# ROS-Robot-Controller.net
KiCad netlist of a schematic drawn in Altium Designer
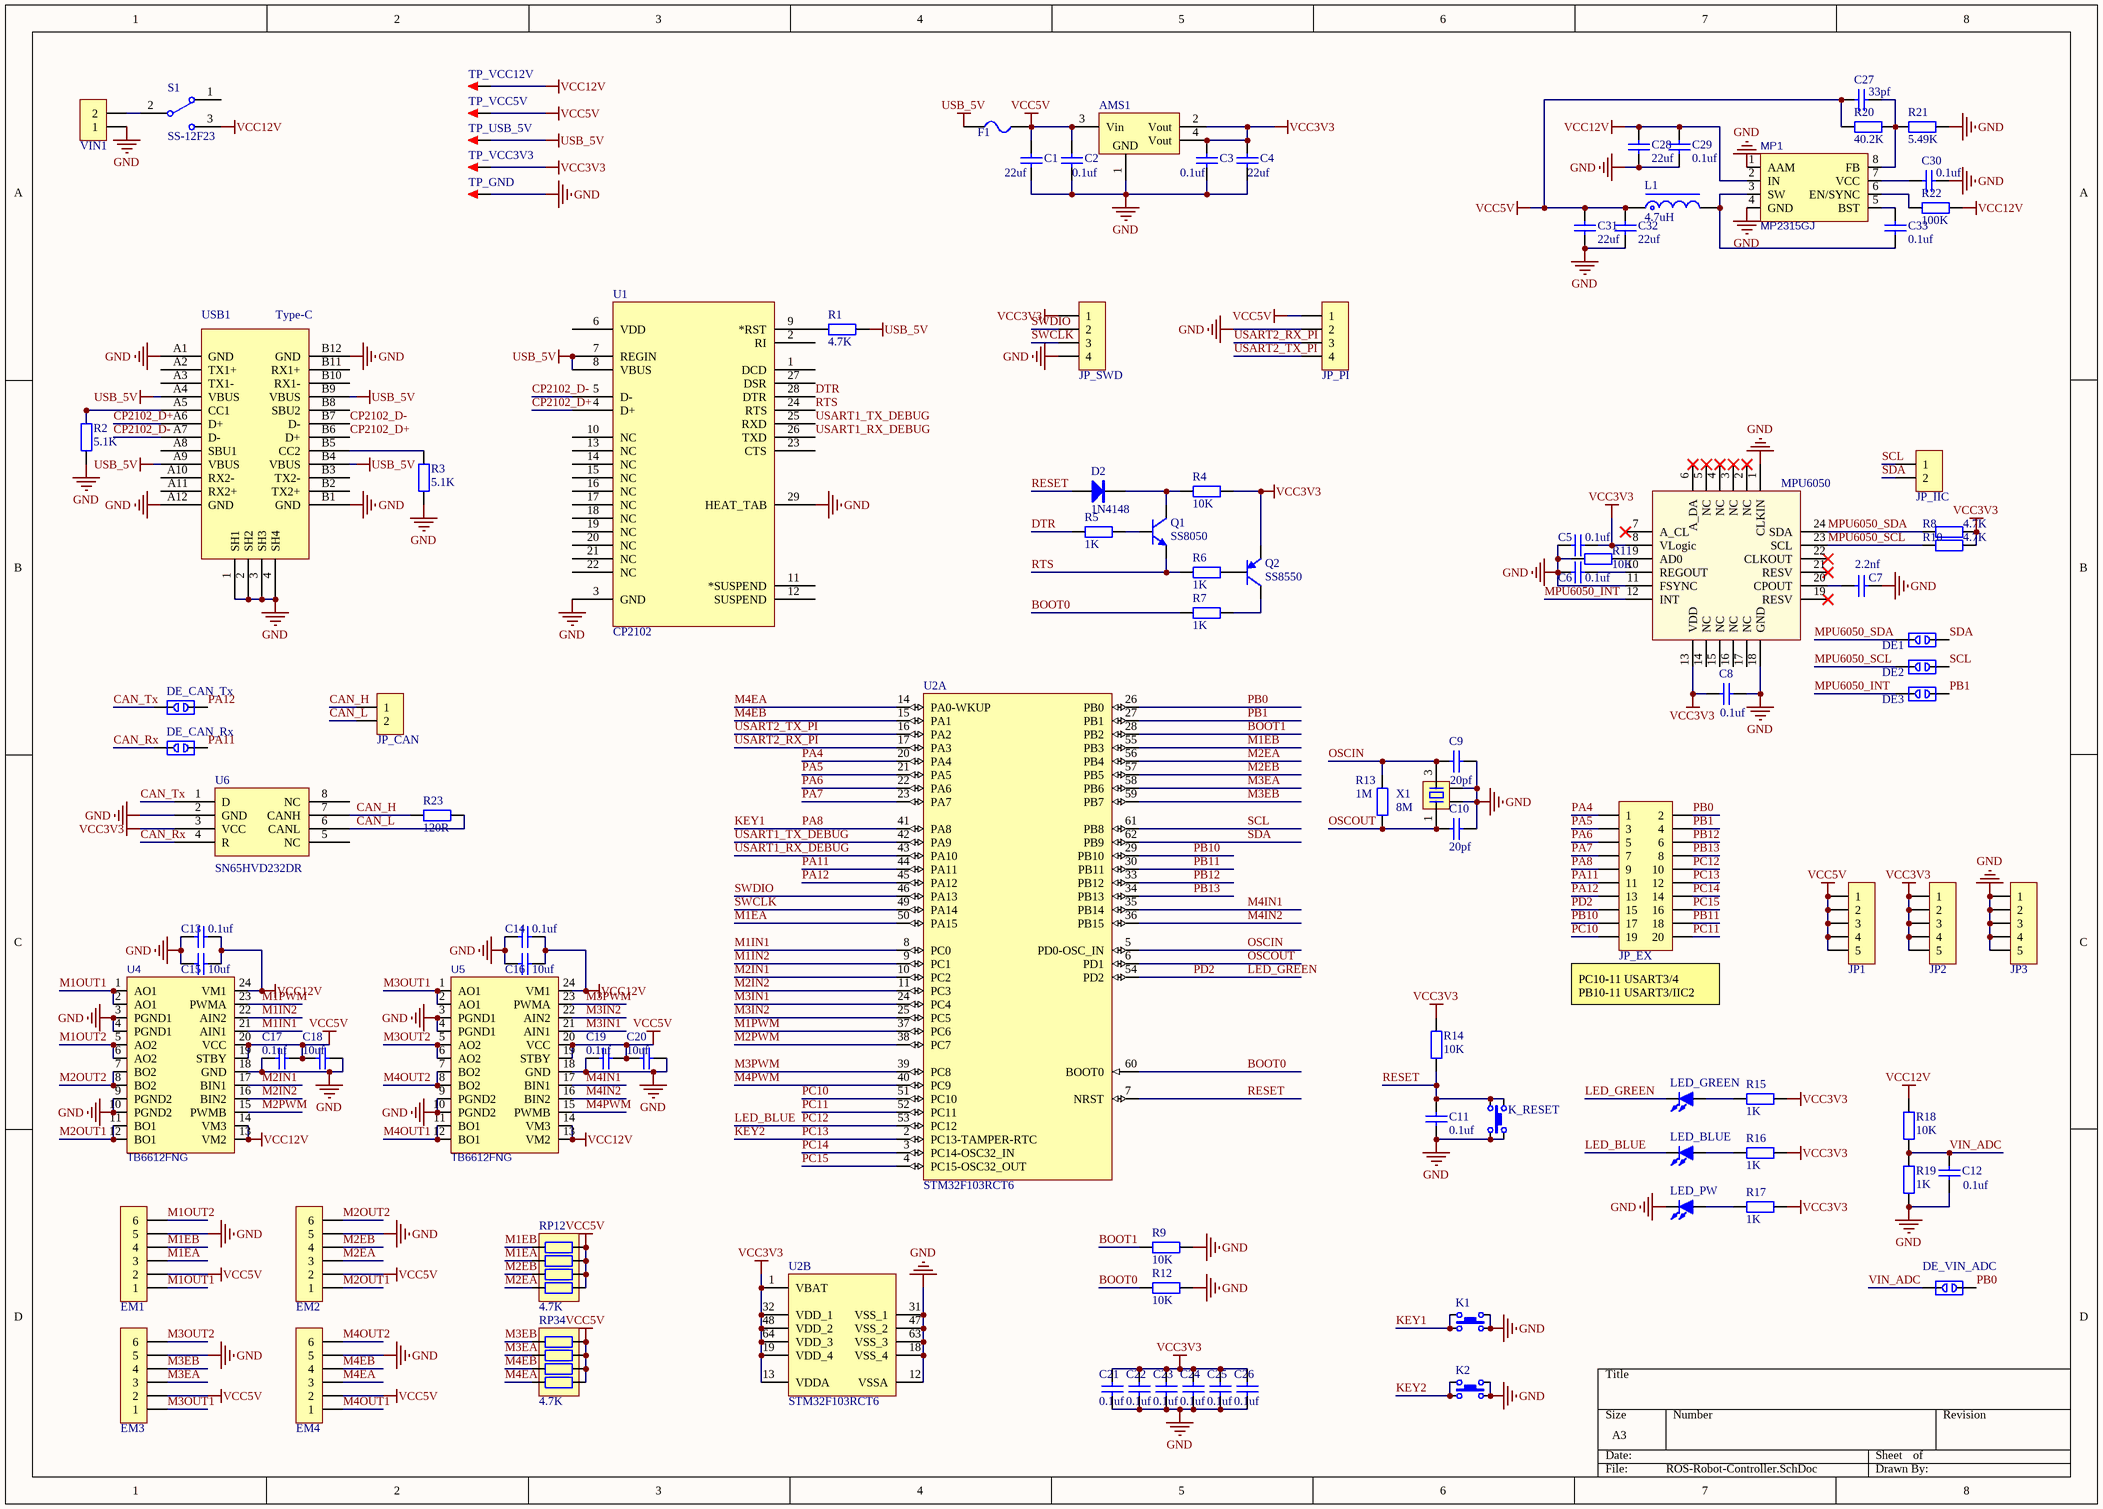
[diagram p0: ROS-Robot-Controller.SchDoc]

(export (version "E")
  (design (tool "Eeschema 10.0.6"))
  (components
    (comp (ref "AMS1")
      (value "AMS1117-3V3")
      (footprint "SOT223_L")
      (description "三端稳压芯片")
      (libsource (lib "1.1 - 电源类芯片") (part "AMS1117"))
    )
    (comp (ref "C1")
      (value "22uf")
      (footprint "C0603_L")
      (description "贴片电容")
      (libsource (lib "0.1 - 电阻-电容-电感-电位器") (part "C"))
    )
    (comp (ref "C2")
      (value "0.1uf")
      (footprint "C0603_L")
      (description "贴片电容")
      (libsource (lib "0.1 - 电阻-电容-电感-电位器") (part "C"))
    )
    (comp (ref "C3")
      (value "0.1uf")
      (footprint "C0603_L")
      (description "贴片电容")
      (libsource (lib "0.1 - 电阻-电容-电感-电位器") (part "C"))
    )
    (comp (ref "C4")
      (value "22uf")
      (footprint "C0603_L")
      (description "贴片电容")
      (libsource (lib "0.1 - 电阻-电容-电感-电位器") (part "C"))
    )
    (comp (ref "C5")
      (value "0.1uf")
      (footprint "C0402_L")
      (description "贴片电容")
      (libsource (lib "0.1 - 电阻-电容-电感-电位器") (part "C"))
    )
    (comp (ref "C6")
      (value "0.1uf")
      (footprint "C0402_L")
      (description "贴片电容")
      (libsource (lib "0.1 - 电阻-电容-电感-电位器") (part "C"))
    )
    (comp (ref "C7")
      (value "2.2nf")
      (footprint "C0402_L")
      (description "贴片电容")
      (libsource (lib "0.1 - 电阻-电容-电感-电位器") (part "C"))
    )
    (comp (ref "C8")
      (value "0.1uf")
      (footprint "C0402_L")
      (description "贴片电容")
      (libsource (lib "0.1 - 电阻-电容-电感-电位器") (part "C"))
    )
    (comp (ref "C9")
      (value "20pf")
      (footprint "C0402_L")
      (description "贴片电容")
      (libsource (lib "0.1 - 电阻-电容-电感-电位器") (part "C"))
    )
    (comp (ref "C10")
      (value "20pf")
      (footprint "C0402_L")
      (description "贴片电容")
      (libsource (lib "0.1 - 电阻-电容-电感-电位器") (part "C"))
    )
    (comp (ref "C11")
      (value "0.1uf")
      (footprint "C0402_L")
      (description "贴片电容")
      (libsource (lib "0.1 - 电阻-电容-电感-电位器") (part "C"))
    )
    (comp (ref "C12")
      (value "0.1uf")
      (footprint "C0603_L")
      (description "贴片电容")
      (libsource (lib "0.1 - 电阻-电容-电感-电位器") (part "C"))
    )
    (comp (ref "C13")
      (value "0.1uf")
      (footprint "C0603_L")
      (description "贴片电容")
      (libsource (lib "0.1 - 电阻-电容-电感-电位器") (part "C"))
    )
    (comp (ref "C14")
      (value "0.1uf")
      (footprint "C0603_L")
      (description "贴片电容")
      (libsource (lib "0.1 - 电阻-电容-电感-电位器") (part "C"))
    )
    (comp (ref "C15")
      (value "10uf")
      (footprint "C0603_L")
      (description "贴片电容")
      (libsource (lib "0.1 - 电阻-电容-电感-电位器") (part "C"))
    )
    (comp (ref "C16")
      (value "10uf")
      (footprint "C0603_L")
      (description "贴片电容")
      (libsource (lib "0.1 - 电阻-电容-电感-电位器") (part "C"))
    )
    (comp (ref "C17")
      (value "0.1uf")
      (footprint "C0402_L")
      (description "贴片电容")
      (libsource (lib "0.1 - 电阻-电容-电感-电位器") (part "C"))
    )
    (comp (ref "C18")
      (value "10uf")
      (footprint "C0402_L")
      (description "贴片电容")
      (libsource (lib "0.1 - 电阻-电容-电感-电位器") (part "C"))
    )
    (comp (ref "C19")
      (value "0.1uf")
      (footprint "C0402_L")
      (description "贴片电容")
      (libsource (lib "0.1 - 电阻-电容-电感-电位器") (part "C"))
    )
    (comp (ref "C20")
      (value "10uf")
      (footprint "C0402_L")
      (description "贴片电容")
      (libsource (lib "0.1 - 电阻-电容-电感-电位器") (part "C"))
    )
    (comp (ref "C21")
      (value "0.1uf")
      (footprint "C0402_L")
      (description "贴片电容")
      (libsource (lib "0.1 - 电阻-电容-电感-电位器") (part "C"))
    )
    (comp (ref "C22")
      (value "0.1uf")
      (footprint "C0402_L")
      (description "贴片电容")
      (libsource (lib "0.1 - 电阻-电容-电感-电位器") (part "C"))
    )
    (comp (ref "C23")
      (value "0.1uf")
      (footprint "C0402_L")
      (description "贴片电容")
      (libsource (lib "0.1 - 电阻-电容-电感-电位器") (part "C"))
    )
    (comp (ref "C24")
      (value "0.1uf")
      (footprint "C0402_L")
      (description "贴片电容")
      (libsource (lib "0.1 - 电阻-电容-电感-电位器") (part "C"))
    )
    (comp (ref "C25")
      (value "0.1uf")
      (footprint "C0402_L")
      (description "贴片电容")
      (libsource (lib "0.1 - 电阻-电容-电感-电位器") (part "C"))
    )
    (comp (ref "C26")
      (value "0.1uf")
      (footprint "C0402_L")
      (description "贴片电容")
      (libsource (lib "0.1 - 电阻-电容-电感-电位器") (part "C"))
    )
    (comp (ref "C27")
      (value "33pf")
      (footprint "C0603_L")
      (description "贴片电容")
      (libsource (lib "0.1 - 电阻-电容-电感-电位器") (part "C"))
    )
    (comp (ref "C28")
      (value "22uf")
      (footprint "C0805_L")
      (description "贴片电容")
      (libsource (lib "0.1 - 电阻-电容-电感-电位器") (part "C"))
    )
    (comp (ref "C29")
      (value "0.1uf")
      (footprint "C0805_L")
      (description "贴片电容")
      (libsource (lib "0.1 - 电阻-电容-电感-电位器") (part "C"))
    )
    (comp (ref "C30")
      (value "0.1uf")
      (footprint "C0603_L")
      (description "贴片电容")
      (libsource (lib "0.1 - 电阻-电容-电感-电位器") (part "C"))
    )
    (comp (ref "C31")
      (value "22uf")
      (footprint "C0603_L")
      (description "贴片电容")
      (libsource (lib "0.1 - 电阻-电容-电感-电位器") (part "C"))
    )
    (comp (ref "C32")
      (value "22uf")
      (footprint "C0603_L")
      (description "贴片电容")
      (libsource (lib "0.1 - 电阻-电容-电感-电位器") (part "C"))
    )
    (comp (ref "C33")
      (value "0.1uf")
      (footprint "C0603_L")
      (description "贴片电容")
      (libsource (lib "0.1 - 电阻-电容-电感-电位器") (part "C"))
    )
    (comp (ref "D2")
      (value "1N4148")
      (footprint "SOD-323")
      (description "开关二极管")
      (libsource (lib "0.2 - 二极管-TVS-整流桥") (part "1N4148"))
    )
    (comp (ref "DE1")
      (value "DEBUG PAD")
      (footprint "DEBUG_B")
      (description "调试断点焊盘")
      (libsource (lib "0.7 - 常用按键-开关-蜂鸣器-电池-测试点") (part "DEBUG"))
    )
    (comp (ref "DE2")
      (value "DEBUG PAD")
      (footprint "DEBUG_B")
      (description "调试断点焊盘")
      (libsource (lib "0.7 - 常用按键-开关-蜂鸣器-电池-测试点") (part "DEBUG"))
    )
    (comp (ref "DE3")
      (value "DEBUG PAD")
      (footprint "DEBUG_B")
      (description "调试断点焊盘")
      (libsource (lib "0.7 - 常用按键-开关-蜂鸣器-电池-测试点") (part "DEBUG"))
    )
    (comp (ref "DE_CAN_Rx")
      (value "DEBUG PAD")
      (footprint "DEBUG_B")
      (description "调试断点焊盘")
      (libsource (lib "0.7 - 常用按键-开关-蜂鸣器-电池-测试点") (part "DEBUG"))
    )
    (comp (ref "DE_CAN_Tx")
      (value "DEBUG PAD")
      (footprint "DEBUG_B")
      (description "调试断点焊盘")
      (libsource (lib "0.7 - 常用按键-开关-蜂鸣器-电池-测试点") (part "DEBUG"))
    )
    (comp (ref "DE_VIN_ADC")
      (value "DEBUG PAD")
      (footprint "DEBUG_B")
      (description "调试断点焊盘")
      (libsource (lib "0.7 - 常用按键-开关-蜂鸣器-电池-测试点") (part "DEBUG"))
    )
    (comp (ref "EM1")
      (value "HDR-1X6")
      (footprint "XH2.54-LI-6P")
      (description "6P接插件")
      (libsource (lib "5.4 - 接插件-脚距2.54 (100mil) ") (part "Header 6"))
    )
    (comp (ref "EM2")
      (value "HDR-1X6")
      (footprint "XH2.54-LI-6P")
      (description "6P接插件")
      (libsource (lib "5.4 - 接插件-脚距2.54 (100mil) ") (part "Header 6"))
    )
    (comp (ref "EM3")
      (value "HDR-1X6")
      (footprint "XH2.54-LI-6P")
      (description "6P接插件")
      (libsource (lib "5.4 - 接插件-脚距2.54 (100mil) ") (part "Header 6"))
    )
    (comp (ref "EM4")
      (value "HDR-1X6")
      (footprint "XH2.54-LI-6P")
      (description "6P接插件")
      (libsource (lib "5.4 - 接插件-脚距2.54 (100mil) ") (part "Header 6"))
    )
    (comp (ref "F1")
      (value "MSMD200-8V 2A")
      (footprint "FU 0603")
      (description "贴片保险丝")
      (libsource (lib "0.5 - 保险丝-晶振-光耦") (part "FU"))
    )
    (comp (ref "JP1")
      (value "HDR-1X5")
      (footprint "HDR2.54-LI-5P")
      (description "5P接插件")
      (libsource (lib "5.4 - 接插件-脚距2.54 (100mil) ") (part "Header 5"))
    )
    (comp (ref "JP2")
      (value "HDR-1X5")
      (footprint "HDR2.54-LI-5P")
      (description "5P接插件")
      (libsource (lib "5.4 - 接插件-脚距2.54 (100mil) ") (part "Header 5"))
    )
    (comp (ref "JP3")
      (value "HDR-1X5")
      (footprint "HDR2.54-LI-5P")
      (description "5P接插件")
      (libsource (lib "5.4 - 接插件-脚距2.54 (100mil) ") (part "Header 5"))
    )
    (comp (ref "JP_CAN")
      (value "HDR-1X2")
      (footprint "HDR2.54-LI-2P")
      (description "2P接插件")
      (libsource (lib "5.4 - 接插件-脚距2.54 (100mil) ") (part "Header 2"))
    )
    (comp (ref "JP_EX")
      (value "Header 2X10")
      (footprint "HDR2.54-LI-2x10P")
      (description "10*2P接插件")
      (libsource (lib "5.4 - 接插件-脚距2.54 (100mil) ") (part "Header 10X2"))
    )
    (comp (ref "JP_IIC")
      (value "HDR-1X2")
      (footprint "HDR2.54-LI-2P")
      (description "2P接插件")
      (libsource (lib "5.4 - 接插件-脚距2.54 (100mil) ") (part "Header 2"))
    )
    (comp (ref "JP_PI")
      (value "HDR-1X4")
      (footprint "HDR2.54-LI-4P")
      (description "4P接插件")
      (libsource (lib "5.4 - 接插件-脚距2.54 (100mil) ") (part "Header 4"))
    )
    (comp (ref "JP_SWD")
      (value "HDR-1X4")
      (footprint "XH2.54-WI-4P")
      (description "4P接插件")
      (libsource (lib "5.4 - 接插件-脚距2.54 (100mil) ") (part "Header 4"))
    )
    (comp (ref "K1")
      (value "TACT 4P")
      (footprint "SW-SMD_4P-L4.2-W3.3-P2.15-LS5.1")
      (description "Button")
      (libsource (lib "KitSprout") (part "ButtonTACT"))
    )
    (comp (ref "K2")
      (value "TACT 4P")
      (footprint "SW-SMD_4P-L4.2-W3.3-P2.15-LS5.1")
      (description "Button")
      (libsource (lib "KitSprout") (part "ButtonTACT"))
    )
    (comp (ref "K_RESET")
      (value "TACT 4P")
      (footprint "SW-SMD_4P-L4.2-W3.3-P2.15-LS5.1")
      (description "Button")
      (libsource (lib "KitSprout") (part "ButtonTACT"))
    )
    (comp (ref "L1")
      (value "4.7uH")
      (footprint "L-SMD-0420")
      (description "一体成型电感")
      (libsource (lib "0.1 - 电阻-电容-电感-电位器") (part "L-Molding Choke"))
    )
    (comp (ref "LED_BLUE")
      (value "红色")
      (footprint "LED_0402_RED")
      (description "贴片LED")
      (libsource (lib "0.3 - LED发光二极管") (part "LED-SMD"))
    )
    (comp (ref "LED_GREEN")
      (value "红色")
      (footprint "LED_0402_RED")
      (description "贴片LED")
      (libsource (lib "0.3 - LED发光二极管") (part "LED-SMD"))
    )
    (comp (ref "LED_PW")
      (value "红色")
      (footprint "LED_0402_RED")
      (description "贴片LED")
      (libsource (lib "0.3 - LED发光二极管") (part "LED-SMD"))
    )
    (comp (ref "MP1")
      (value "MP2315GJ")
      (footprint "SOT23-8N")
      (description "3A/24V DC-DC降压芯片")
      (libsource (lib "1.1 - 电源类芯片") (part "MP2315"))
    )
    (comp (ref "Q1")
      (value "SS8050")
      (footprint "SOT23-3N")
      (description "高频放大-NPN型")
      (libsource (lib "0.4 - 三极管-场效应管-可控硅") (part "8050-SMD"))
    )
    (comp (ref "Q2")
      (value "SS8550")
      (footprint "SOT23-3N")
      (description "高频放大-PNP型")
      (libsource (lib "0.4 - 三极管-场效应管-可控硅") (part "8550-SMD"))
    )
    (comp (ref "R1")
      (value "4.7K")
      (footprint "R0402_L")
      (description "贴片电阻")
      (libsource (lib "0.1 - 电阻-电容-电感-电位器") (part "R"))
    )
    (comp (ref "R2")
      (value "5.1K")
      (footprint "R0402_L")
      (description "贴片电阻")
      (libsource (lib "0.1 - 电阻-电容-电感-电位器") (part "R"))
    )
    (comp (ref "R3")
      (value "5.1K")
      (footprint "R0402_L")
      (description "贴片电阻")
      (libsource (lib "0.1 - 电阻-电容-电感-电位器") (part "R"))
    )
    (comp (ref "R4")
      (value "10K")
      (footprint "R0402_L")
      (description "贴片电阻")
      (libsource (lib "0.1 - 电阻-电容-电感-电位器") (part "R"))
    )
    (comp (ref "R5")
      (value "1K")
      (footprint "R0402_L")
      (description "贴片电阻")
      (libsource (lib "0.1 - 电阻-电容-电感-电位器") (part "R"))
    )
    (comp (ref "R6")
      (value "1K")
      (footprint "R0402_L")
      (description "贴片电阻")
      (libsource (lib "0.1 - 电阻-电容-电感-电位器") (part "R"))
    )
    (comp (ref "R7")
      (value "1K")
      (footprint "R0402_L")
      (description "贴片电阻")
      (libsource (lib "0.1 - 电阻-电容-电感-电位器") (part "R"))
    )
    (comp (ref "R8")
      (value "4.7K")
      (footprint "R0402_L")
      (description "贴片电阻")
      (libsource (lib "0.1 - 电阻-电容-电感-电位器") (part "R"))
    )
    (comp (ref "R9")
      (value "10K")
      (footprint "R0402_L")
      (description "贴片电阻")
      (libsource (lib "0.1 - 电阻-电容-电感-电位器") (part "R"))
    )
    (comp (ref "R10")
      (value "4.7K")
      (footprint "R0402_L")
      (description "贴片电阻")
      (libsource (lib "0.1 - 电阻-电容-电感-电位器") (part "R"))
    )
    (comp (ref "R11")
      (value "10K")
      (footprint "R0402_L")
      (description "贴片电阻")
      (libsource (lib "0.1 - 电阻-电容-电感-电位器") (part "R"))
    )
    (comp (ref "R12")
      (value "10K")
      (footprint "R0402_L")
      (description "贴片电阻")
      (libsource (lib "0.1 - 电阻-电容-电感-电位器") (part "R"))
    )
    (comp (ref "R13")
      (value "1M")
      (footprint "R0402_L")
      (description "贴片电阻")
      (libsource (lib "0.1 - 电阻-电容-电感-电位器") (part "R"))
    )
    (comp (ref "R14")
      (value "10K")
      (footprint "R0402_L")
      (description "贴片电阻")
      (libsource (lib "0.1 - 电阻-电容-电感-电位器") (part "R"))
    )
    (comp (ref "R15")
      (value "1K")
      (footprint "R0402_L")
      (description "贴片电阻")
      (libsource (lib "0.1 - 电阻-电容-电感-电位器") (part "R"))
    )
    (comp (ref "R16")
      (value "1K")
      (footprint "R0402_L")
      (description "贴片电阻")
      (libsource (lib "0.1 - 电阻-电容-电感-电位器") (part "R"))
    )
    (comp (ref "R17")
      (value "1K")
      (footprint "R0402_L")
      (description "贴片电阻")
      (libsource (lib "0.1 - 电阻-电容-电感-电位器") (part "R"))
    )
    (comp (ref "R18")
      (value "10K")
      (footprint "R0603_L")
      (description "贴片电阻")
      (libsource (lib "0.1 - 电阻-电容-电感-电位器") (part "R"))
    )
    (comp (ref "R19")
      (value "1K")
      (footprint "R0603_L")
      (description "贴片电阻")
      (libsource (lib "0.1 - 电阻-电容-电感-电位器") (part "R"))
    )
    (comp (ref "R20")
      (value "40.2K")
      (footprint "R0603_L")
      (description "贴片电阻")
      (libsource (lib "0.1 - 电阻-电容-电感-电位器") (part "R"))
    )
    (comp (ref "R21")
      (value "5.49K")
      (footprint "R0603_L")
      (description "贴片电阻")
      (libsource (lib "0.1 - 电阻-电容-电感-电位器") (part "R"))
    )
    (comp (ref "R22")
      (value "100K")
      (footprint "R0603_L")
      (description "贴片电阻")
      (libsource (lib "0.1 - 电阻-电容-电感-电位器") (part "R"))
    )
    (comp (ref "R23")
      (value "120R")
      (footprint "R0402_L")
      (description "贴片电阻")
      (libsource (lib "0.1 - 电阻-电容-电感-电位器") (part "R"))
    )
    (comp (ref "RP12")
      (value "4.7K")
      (footprint "RCA-8P4R-0402")
      (description "贴片4P排阻")
      (libsource (lib "0.1 - 电阻-电容-电感-电位器") (part "R-8P4R"))
    )
    (comp (ref "RP34")
      (value "4.7K")
      (footprint "RCA-8P4R-0402")
      (description "贴片4P排阻")
      (libsource (lib "0.1 - 电阻-电容-电感-电位器") (part "R-8P4R"))
    )
    (comp (ref "S1")
      (value "SS-12F23")
      (footprint "SS-12D10")
      (description "1路波动开关")
      (libsource (lib "0.7 - 常用按键-开关-蜂鸣器-电池-测试点") (part "SSW-1P"))
    )
    (comp (ref "TP_GND")
      (value "TEST")
      (footprint "TEST 1")
      (description "测试点")
      (libsource (lib "0.7 - 常用按键-开关-蜂鸣器-电池-测试点") (part "TEST"))
    )
    (comp (ref "TP_USB_5V")
      (value "TEST")
      (footprint "TEST 1")
      (description "测试点")
      (libsource (lib "0.7 - 常用按键-开关-蜂鸣器-电池-测试点") (part "TEST"))
    )
    (comp (ref "TP_VCC3V3")
      (value "TEST")
      (footprint "TEST 1")
      (description "测试点")
      (libsource (lib "0.7 - 常用按键-开关-蜂鸣器-电池-测试点") (part "TEST"))
    )
    (comp (ref "TP_VCC5V")
      (value "TEST")
      (footprint "TEST 1")
      (description "测试点")
      (libsource (lib "0.7 - 常用按键-开关-蜂鸣器-电池-测试点") (part "TEST"))
    )
    (comp (ref "TP_VCC12V")
      (value "TEST")
      (footprint "TEST 1")
      (description "测试点")
      (libsource (lib "0.7 - 常用按键-开关-蜂鸣器-电池-测试点") (part "TEST"))
    )
    (comp (ref "U1")
      (value "CP2102")
      (footprint "QFN-28")
      (description "USB转TTL")
      (libsource (lib "mLib") (part "CP2102"))
    )
    (comp (ref "U2")
      (value "STM32F103RCT6")
      (footprint "LQFP64_N")
      (libsource (lib "2.4 - STM32 F1系列单片机") (part "STM32F103RCT6"))
    )
    (comp (ref "U3")
      (value "MPU6050")
      (footprint "QFN-24")
      (description "六轴传感器")
      (libsource (lib "mLib") (part "MPU6050"))
    )
    (comp (ref "U4")
      (value "TB6612FNG")
      (footprint "SSOP24_M")
      (description "电机驱动")
      (libsource (lib "1.0 - 常见芯片") (part "TB6612FNG"))
    )
    (comp (ref "U5")
      (value "TB6612FNG")
      (footprint "SSOP24_M")
      (description "电机驱动")
      (libsource (lib "1.0 - 常见芯片") (part "TB6612FNG"))
    )
    (comp (ref "U6")
      (value "SN65HVD232D")
      (footprint "SO-8")
      (fields
        (field (name "MANUFACTURER") "Texas Instruments")
        (field (name "MANUFACTURER PART NUMBER") "SN65HVD232DR")
      )
      (libsource (lib "MyPcbLib") (part "SN65HVD232D"))
    )
    (comp (ref "USB1")
      (value "Type-C")
      (footprint "Type-C-TOP")
      (libsource (lib "MyPcbLib") (part "USB-Type-C-TOP"))
    )
    (comp (ref "VIN1")
      (value "HDR-1X2")
      (footprint "KF301-5.0-2P")
      (description "2P接插件")
      (libsource (lib "6.0 - 接插件-脚距5.0") (part "Header 2"))
    )
    (comp (ref "X1")
      (value "8M")
      (footprint "OSC 3225-4P")
      (description "4脚无源晶振")
      (libsource (lib "0.5 - 保险丝-晶振-光耦") (part "XTAL-4P"))
    )
  )
  (nets
    (net (code "1") (name "/BOOT0") (class "Default")
      (node (ref "R12") (pin "1") (pinfunction "1_1") (pintype "passive"))
      (node (ref "R7") (pin "2") (pinfunction "2_2") (pintype "passive"))
      (node (ref "U2") (pin "60") (pinfunction "BOOT0_60") (pintype "input"))
    )
    (net (code "2") (name "/BOOT1") (class "Default")
      (node (ref "R9") (pin "1") (pinfunction "1_1") (pintype "passive"))
      (node (ref "U2") (pin "28") (pinfunction "PB2_28") (pintype "bidirectional"))
    )
    (net (code "3") (name "/CAN_H") (class "Default")
      (node (ref "JP_CAN") (pin "1") (pinfunction "1_1") (pintype "passive"))
      (node (ref "R23") (pin "1") (pinfunction "1_1") (pintype "passive"))
      (node (ref "U6") (pin "7") (pinfunction "CANH_7") (pintype "passive"))
    )
    (net (code "4") (name "/CAN_L") (class "Default")
      (node (ref "JP_CAN") (pin "2") (pinfunction "2_2") (pintype "passive"))
      (node (ref "R23") (pin "2") (pinfunction "2_2") (pintype "passive"))
      (node (ref "U6") (pin "6") (pinfunction "CANL_6") (pintype "passive"))
    )
    (net (code "5") (name "/CAN_Rx") (class "Default")
      (node (ref "DE_CAN_Rx") (pin "1") (pinfunction "1_1") (pintype "passive"))
      (node (ref "U6") (pin "4") (pinfunction "R_4") (pintype "passive"))
    )
    (net (code "6") (name "/CAN_Tx") (class "Default")
      (node (ref "DE_CAN_Tx") (pin "1") (pinfunction "1_1") (pintype "passive"))
      (node (ref "U6") (pin "1") (pinfunction "D_1") (pintype "passive"))
    )
    (net (code "7") (name "/CP2102_D+") (class "Default")
      (node (ref "U1") (pin "4") (pinfunction "D+_4") (pintype "passive"))
      (node (ref "USB1") (pin "A6") (pinfunction "D+_A6") (pintype "passive"))
      (node (ref "USB1") (pin "B6") (pinfunction "D+_B6") (pintype "passive"))
    )
    (net (code "8") (name "/CP2102_D-") (class "Default")
      (node (ref "U1") (pin "5") (pinfunction "D-_5") (pintype "passive"))
      (node (ref "USB1") (pin "A7") (pinfunction "D-_A7") (pintype "passive"))
      (node (ref "USB1") (pin "B7") (pinfunction "D-_B7") (pintype "passive"))
    )
    (net (code "9") (name "/DTR") (class "Default")
      (node (ref "R5") (pin "1") (pinfunction "1_1") (pintype "passive"))
      (node (ref "U1") (pin "28") (pinfunction "DTR_28") (pintype "passive"))
    )
    (net (code "10") (name "/KEY1") (class "Default")
      (node (ref "JP_EX") (pin "9") (pinfunction "9_9") (pintype "passive"))
      (node (ref "K1") (pin "1") (pinfunction "1_1") (pintype "passive"))
      (node (ref "K1") (pin "3") (pinfunction "3_3") (pintype "passive"))
      (node (ref "U2") (pin "41") (pinfunction "PA8_41") (pintype "bidirectional"))
    )
    (net (code "11") (name "/KEY2") (class "Default")
      (node (ref "JP_EX") (pin "12") (pinfunction "12_12") (pintype "passive"))
      (node (ref "K2") (pin "1") (pinfunction "1_1") (pintype "passive"))
      (node (ref "K2") (pin "3") (pinfunction "3_3") (pintype "passive"))
      (node (ref "U2") (pin "2") (pinfunction "PC13-TAMPER-RTC_2") (pintype "bidirectional"))
    )
    (net (code "12") (name "/LED_BLUE") (class "Default")
      (node (ref "JP_EX") (pin "10") (pinfunction "10_10") (pintype "passive"))
      (node (ref "LED_BLUE") (pin "2") (pinfunction "K_2") (pintype "passive"))
      (node (ref "U2") (pin "53") (pinfunction "PC12_53") (pintype "bidirectional"))
    )
    (net (code "13") (name "/LED_GREEN") (class "Default")
      (node (ref "JP_EX") (pin "15") (pinfunction "15_15") (pintype "passive"))
      (node (ref "LED_GREEN") (pin "2") (pinfunction "K_2") (pintype "passive"))
      (node (ref "U2") (pin "54") (pinfunction "PD2_54") (pintype "bidirectional"))
    )
    (net (code "14") (name "/M1EA") (class "Default")
      (node (ref "EM1") (pin "3") (pinfunction "3_3") (pintype "passive"))
      (node (ref "RP12") (pin "2") (pinfunction "2_2") (pintype "passive"))
      (node (ref "U2") (pin "50") (pinfunction "PA15_50") (pintype "bidirectional"))
    )
    (net (code "15") (name "/M1EB") (class "Default")
      (node (ref "EM1") (pin "4") (pinfunction "4_4") (pintype "passive"))
      (node (ref "RP12") (pin "1") (pinfunction "1_1") (pintype "passive"))
      (node (ref "U2") (pin "55") (pinfunction "PB3_55") (pintype "bidirectional"))
    )
    (net (code "16") (name "/M1IN1") (class "Default")
      (node (ref "U2") (pin "8") (pinfunction "PC0_8") (pintype "bidirectional"))
      (node (ref "U4") (pin "21") (pinfunction "AIN1_21") (pintype "passive"))
    )
    (net (code "17") (name "/M1IN2") (class "Default")
      (node (ref "U2") (pin "9") (pinfunction "PC1_9") (pintype "bidirectional"))
      (node (ref "U4") (pin "22") (pinfunction "AIN2_22") (pintype "passive"))
    )
    (net (code "18") (name "/M1OUT1") (class "Default")
      (node (ref "EM1") (pin "1") (pinfunction "1_1") (pintype "passive"))
      (node (ref "U4") (pin "1") (pinfunction "AO1_1") (pintype "passive"))
      (node (ref "U4") (pin "2") (pinfunction "AO1_2") (pintype "passive"))
    )
    (net (code "19") (name "/M1OUT2") (class "Default")
      (node (ref "EM1") (pin "6") (pinfunction "6_6") (pintype "passive"))
      (node (ref "U4") (pin "5") (pinfunction "AO2_5") (pintype "passive"))
      (node (ref "U4") (pin "6") (pinfunction "AO2_6") (pintype "passive"))
    )
    (net (code "20") (name "/M1PWM") (class "Default")
      (node (ref "U2") (pin "37") (pinfunction "PC6_37") (pintype "bidirectional"))
      (node (ref "U4") (pin "23") (pinfunction "PWMA_23") (pintype "passive"))
    )
    (net (code "21") (name "/M2EA") (class "Default")
      (node (ref "EM2") (pin "3") (pinfunction "3_3") (pintype "passive"))
      (node (ref "RP12") (pin "4") (pinfunction "4_4") (pintype "passive"))
      (node (ref "U2") (pin "56") (pinfunction "PB4_56") (pintype "bidirectional"))
    )
    (net (code "22") (name "/M2EB") (class "Default")
      (node (ref "EM2") (pin "4") (pinfunction "4_4") (pintype "passive"))
      (node (ref "RP12") (pin "3") (pinfunction "3_3") (pintype "passive"))
      (node (ref "U2") (pin "57") (pinfunction "PB5_57") (pintype "bidirectional"))
    )
    (net (code "23") (name "/M2IN1") (class "Default")
      (node (ref "U2") (pin "10") (pinfunction "PC2_10") (pintype "bidirectional"))
      (node (ref "U4") (pin "17") (pinfunction "BIN1_17") (pintype "passive"))
    )
    (net (code "24") (name "/M2IN2") (class "Default")
      (node (ref "U2") (pin "11") (pinfunction "PC3_11") (pintype "bidirectional"))
      (node (ref "U4") (pin "16") (pinfunction "BIN2_16") (pintype "passive"))
    )
    (net (code "25") (name "/M2OUT1") (class "Default")
      (node (ref "EM2") (pin "1") (pinfunction "1_1") (pintype "passive"))
      (node (ref "U4") (pin "11") (pinfunction "BO1_11") (pintype "passive"))
      (node (ref "U4") (pin "12") (pinfunction "BO1_12") (pintype "passive"))
    )
    (net (code "26") (name "/M2OUT2") (class "Default")
      (node (ref "EM2") (pin "6") (pinfunction "6_6") (pintype "passive"))
      (node (ref "U4") (pin "7") (pinfunction "BO2_7") (pintype "passive"))
      (node (ref "U4") (pin "8") (pinfunction "BO2_8") (pintype "passive"))
    )
    (net (code "27") (name "/M2PWM") (class "Default")
      (node (ref "U2") (pin "38") (pinfunction "PC7_38") (pintype "bidirectional"))
      (node (ref "U4") (pin "15") (pinfunction "PWMB_15") (pintype "passive"))
    )
    (net (code "28") (name "/M3EA") (class "Default")
      (node (ref "EM3") (pin "3") (pinfunction "3_3") (pintype "passive"))
      (node (ref "RP34") (pin "2") (pinfunction "2_2") (pintype "passive"))
      (node (ref "U2") (pin "58") (pinfunction "PB6_58") (pintype "bidirectional"))
    )
    (net (code "29") (name "/M3EB") (class "Default")
      (node (ref "EM3") (pin "4") (pinfunction "4_4") (pintype "passive"))
      (node (ref "RP34") (pin "1") (pinfunction "1_1") (pintype "passive"))
      (node (ref "U2") (pin "59") (pinfunction "PB7_59") (pintype "bidirectional"))
    )
    (net (code "30") (name "/M3IN1") (class "Default")
      (node (ref "U2") (pin "24") (pinfunction "PC4_24") (pintype "bidirectional"))
      (node (ref "U5") (pin "21") (pinfunction "AIN1_21") (pintype "passive"))
    )
    (net (code "31") (name "/M3IN2") (class "Default")
      (node (ref "U2") (pin "25") (pinfunction "PC5_25") (pintype "bidirectional"))
      (node (ref "U5") (pin "22") (pinfunction "AIN2_22") (pintype "passive"))
    )
    (net (code "32") (name "/M3OUT1") (class "Default")
      (node (ref "EM3") (pin "1") (pinfunction "1_1") (pintype "passive"))
      (node (ref "U5") (pin "1") (pinfunction "AO1_1") (pintype "passive"))
      (node (ref "U5") (pin "2") (pinfunction "AO1_2") (pintype "passive"))
    )
    (net (code "33") (name "/M3OUT2") (class "Default")
      (node (ref "EM3") (pin "6") (pinfunction "6_6") (pintype "passive"))
      (node (ref "U5") (pin "5") (pinfunction "AO2_5") (pintype "passive"))
      (node (ref "U5") (pin "6") (pinfunction "AO2_6") (pintype "passive"))
    )
    (net (code "34") (name "/M3PWM") (class "Default")
      (node (ref "U2") (pin "39") (pinfunction "PC8_39") (pintype "bidirectional"))
      (node (ref "U5") (pin "23") (pinfunction "PWMA_23") (pintype "passive"))
    )
    (net (code "35") (name "/M4EA") (class "Default")
      (node (ref "EM4") (pin "3") (pinfunction "3_3") (pintype "passive"))
      (node (ref "RP34") (pin "4") (pinfunction "4_4") (pintype "passive"))
      (node (ref "U2") (pin "14") (pinfunction "PA0-WKUP_14") (pintype "bidirectional"))
    )
    (net (code "36") (name "/M4EB") (class "Default")
      (node (ref "EM4") (pin "4") (pinfunction "4_4") (pintype "passive"))
      (node (ref "RP34") (pin "3") (pinfunction "3_3") (pintype "passive"))
      (node (ref "U2") (pin "15") (pinfunction "PA1_15") (pintype "bidirectional"))
    )
    (net (code "37") (name "/M4IN1") (class "Default")
      (node (ref "U2") (pin "35") (pinfunction "PB14_35") (pintype "bidirectional"))
      (node (ref "U5") (pin "17") (pinfunction "BIN1_17") (pintype "passive"))
    )
    (net (code "38") (name "/M4IN2") (class "Default")
      (node (ref "U2") (pin "36") (pinfunction "PB15_36") (pintype "bidirectional"))
      (node (ref "U5") (pin "16") (pinfunction "BIN2_16") (pintype "passive"))
    )
    (net (code "39") (name "/M4OUT1") (class "Default")
      (node (ref "EM4") (pin "1") (pinfunction "1_1") (pintype "passive"))
      (node (ref "U5") (pin "11") (pinfunction "BO1_11") (pintype "passive"))
      (node (ref "U5") (pin "12") (pinfunction "BO1_12") (pintype "passive"))
    )
    (net (code "40") (name "/M4OUT2") (class "Default")
      (node (ref "EM4") (pin "6") (pinfunction "6_6") (pintype "passive"))
      (node (ref "U5") (pin "7") (pinfunction "BO2_7") (pintype "passive"))
      (node (ref "U5") (pin "8") (pinfunction "BO2_8") (pintype "passive"))
    )
    (net (code "41") (name "/M4PWM") (class "Default")
      (node (ref "U2") (pin "40") (pinfunction "PC9_40") (pintype "bidirectional"))
      (node (ref "U5") (pin "15") (pinfunction "PWMB_15") (pintype "passive"))
    )
    (net (code "42") (name "/MPU6050_INT") (class "Default")
      (node (ref "DE3") (pin "1") (pinfunction "1_1") (pintype "passive"))
      (node (ref "U3") (pin "12") (pinfunction "INT_12") (pintype "passive"))
    )
    (net (code "43") (name "/MPU6050_SCL") (class "Default")
      (node (ref "DE2") (pin "1") (pinfunction "1_1") (pintype "passive"))
      (node (ref "R10") (pin "1") (pinfunction "1_1") (pintype "passive"))
      (node (ref "U3") (pin "23") (pinfunction "SCL_23") (pintype "passive"))
    )
    (net (code "44") (name "/MPU6050_SDA") (class "Default")
      (node (ref "DE1") (pin "1") (pinfunction "1_1") (pintype "passive"))
      (node (ref "R8") (pin "1") (pinfunction "1_1") (pintype "passive"))
      (node (ref "U3") (pin "24") (pinfunction "SDA_24") (pintype "passive"))
    )
    (net (code "45") (name "/OSCIN") (class "Default")
      (node (ref "C9") (pin "1") (pinfunction "1_1") (pintype "passive"))
      (node (ref "R13") (pin "2") (pinfunction "2_2") (pintype "passive"))
      (node (ref "U2") (pin "5") (pinfunction "PD0-OSC_IN_5") (pintype "bidirectional"))
      (node (ref "X1") (pin "3") (pinfunction "3_3") (pintype "passive"))
    )
    (net (code "46") (name "/OSCOUT") (class "Default")
      (node (ref "C10") (pin "1") (pinfunction "1_1") (pintype "passive"))
      (node (ref "R13") (pin "1") (pinfunction "1_1") (pintype "passive"))
      (node (ref "U2") (pin "6") (pinfunction "PD1_6") (pintype "bidirectional"))
      (node (ref "X1") (pin "1") (pinfunction "1_1") (pintype "passive"))
    )
    (net (code "47") (name "/PA4") (class "Default")
      (node (ref "JP_EX") (pin "1") (pinfunction "1_1") (pintype "passive"))
      (node (ref "U2") (pin "20") (pinfunction "PA4_20") (pintype "bidirectional"))
    )
    (net (code "48") (name "/PA5") (class "Default")
      (node (ref "JP_EX") (pin "3") (pinfunction "3_3") (pintype "passive"))
      (node (ref "U2") (pin "21") (pinfunction "PA5_21") (pintype "bidirectional"))
    )
    (net (code "49") (name "/PA6") (class "Default")
      (node (ref "JP_EX") (pin "5") (pinfunction "5_5") (pintype "passive"))
      (node (ref "U2") (pin "22") (pinfunction "PA6_22") (pintype "bidirectional"))
    )
    (net (code "50") (name "/PA7") (class "Default")
      (node (ref "JP_EX") (pin "7") (pinfunction "7_7") (pintype "passive"))
      (node (ref "U2") (pin "23") (pinfunction "PA7_23") (pintype "bidirectional"))
    )
    (net (code "51") (name "/PA11") (class "Default")
      (node (ref "DE_CAN_Rx") (pin "2") (pinfunction "2_2") (pintype "passive"))
      (node (ref "JP_EX") (pin "11") (pinfunction "11_11") (pintype "passive"))
      (node (ref "U2") (pin "44") (pinfunction "PA11_44") (pintype "bidirectional"))
    )
    (net (code "52") (name "/PA12") (class "Default")
      (node (ref "DE_CAN_Tx") (pin "2") (pinfunction "2_2") (pintype "passive"))
      (node (ref "JP_EX") (pin "13") (pinfunction "13_13") (pintype "passive"))
      (node (ref "U2") (pin "45") (pinfunction "PA12_45") (pintype "bidirectional"))
    )
    (net (code "53") (name "/PB0") (class "Default")
      (node (ref "DE_VIN_ADC") (pin "2") (pinfunction "2_2") (pintype "passive"))
      (node (ref "JP_EX") (pin "2") (pinfunction "2_2") (pintype "passive"))
      (node (ref "U2") (pin "26") (pinfunction "PB0_26") (pintype "bidirectional"))
    )
    (net (code "54") (name "/PB1") (class "Default")
      (node (ref "DE3") (pin "2") (pinfunction "2_2") (pintype "passive"))
      (node (ref "JP_EX") (pin "4") (pinfunction "4_4") (pintype "passive"))
      (node (ref "U2") (pin "27") (pinfunction "PB1_27") (pintype "bidirectional"))
    )
    (net (code "55") (name "/PB10") (class "Default")
      (node (ref "JP_EX") (pin "17") (pinfunction "17_17") (pintype "passive"))
      (node (ref "U2") (pin "29") (pinfunction "PB10_29") (pintype "bidirectional"))
    )
    (net (code "56") (name "/PB11") (class "Default")
      (node (ref "JP_EX") (pin "18") (pinfunction "18_18") (pintype "passive"))
      (node (ref "U2") (pin "30") (pinfunction "PB11_30") (pintype "bidirectional"))
    )
    (net (code "57") (name "/PB12") (class "Default")
      (node (ref "JP_EX") (pin "6") (pinfunction "6_6") (pintype "passive"))
      (node (ref "U2") (pin "33") (pinfunction "PB12_33") (pintype "bidirectional"))
    )
    (net (code "58") (name "/PB13") (class "Default")
      (node (ref "JP_EX") (pin "8") (pinfunction "8_8") (pintype "passive"))
      (node (ref "U2") (pin "34") (pinfunction "PB13_34") (pintype "bidirectional"))
    )
    (net (code "59") (name "/PC10") (class "Default")
      (node (ref "JP_EX") (pin "19") (pinfunction "19_19") (pintype "passive"))
      (node (ref "U2") (pin "51") (pinfunction "PC10_51") (pintype "bidirectional"))
    )
    (net (code "60") (name "/PC11") (class "Default")
      (node (ref "JP_EX") (pin "20") (pinfunction "20_20") (pintype "passive"))
      (node (ref "U2") (pin "52") (pinfunction "PC11_52") (pintype "bidirectional"))
    )
    (net (code "61") (name "/PC14") (class "Default")
      (node (ref "JP_EX") (pin "14") (pinfunction "14_14") (pintype "passive"))
      (node (ref "U2") (pin "3") (pinfunction "PC14-OSC32_IN_3") (pintype "bidirectional"))
    )
    (net (code "62") (name "/PC15") (class "Default")
      (node (ref "JP_EX") (pin "16") (pinfunction "16_16") (pintype "passive"))
      (node (ref "U2") (pin "4") (pinfunction "PC15-OSC32_OUT_4") (pintype "bidirectional"))
    )
    (net (code "63") (name "/RESET") (class "Default")
      (node (ref "C11") (pin "2") (pinfunction "2_2") (pintype "passive"))
      (node (ref "D2") (pin "1") (pinfunction "A_1") (pintype "passive"))
      (node (ref "K_RESET") (pin "1") (pinfunction "1_1") (pintype "passive"))
      (node (ref "K_RESET") (pin "3") (pinfunction "3_3") (pintype "passive"))
      (node (ref "R14") (pin "1") (pinfunction "1_1") (pintype "passive"))
      (node (ref "U2") (pin "7") (pinfunction "NRST_7") (pintype "bidirectional"))
    )
    (net (code "64") (name "/RTS") (class "Default")
      (node (ref "Q1") (pin "2") (pinfunction "E_2") (pintype "passive"))
      (node (ref "R6") (pin "1") (pinfunction "1_1") (pintype "passive"))
      (node (ref "U1") (pin "24") (pinfunction "RTS_24") (pintype "passive"))
    )
    (net (code "65") (name "/SCL") (class "Default")
      (node (ref "DE2") (pin "2") (pinfunction "2_2") (pintype "passive"))
      (node (ref "JP_IIC") (pin "1") (pinfunction "1_1") (pintype "passive"))
      (node (ref "U2") (pin "61") (pinfunction "PB8_61") (pintype "bidirectional"))
    )
    (net (code "66") (name "/SDA") (class "Default")
      (node (ref "DE1") (pin "2") (pinfunction "2_2") (pintype "passive"))
      (node (ref "JP_IIC") (pin "2") (pinfunction "2_2") (pintype "passive"))
      (node (ref "U2") (pin "62") (pinfunction "PB9_62") (pintype "bidirectional"))
    )
    (net (code "67") (name "/SWCLK") (class "Default")
      (node (ref "JP_SWD") (pin "3") (pinfunction "3_3") (pintype "passive"))
      (node (ref "U2") (pin "49") (pinfunction "PA14_49") (pintype "bidirectional"))
    )
    (net (code "68") (name "/SWDIO") (class "Default")
      (node (ref "JP_SWD") (pin "2") (pinfunction "2_2") (pintype "passive"))
      (node (ref "U2") (pin "46") (pinfunction "PA13_46") (pintype "bidirectional"))
    )
    (net (code "69") (name "/USART1_RX_DEBUG") (class "Default")
      (node (ref "U1") (pin "26") (pinfunction "TXD_26") (pintype "passive"))
      (node (ref "U2") (pin "43") (pinfunction "PA10_43") (pintype "bidirectional"))
    )
    (net (code "70") (name "/USART1_TX_DEBUG") (class "Default")
      (node (ref "U1") (pin "25") (pinfunction "RXD_25") (pintype "passive"))
      (node (ref "U2") (pin "42") (pinfunction "PA9_42") (pintype "bidirectional"))
    )
    (net (code "71") (name "/USART2_RX_PI") (class "Default")
      (node (ref "JP_PI") (pin "3") (pinfunction "3_3") (pintype "passive"))
      (node (ref "U2") (pin "17") (pinfunction "PA3_17") (pintype "bidirectional"))
    )
    (net (code "72") (name "/USART2_TX_PI") (class "Default")
      (node (ref "JP_PI") (pin "4") (pinfunction "4_4") (pintype "passive"))
      (node (ref "U2") (pin "16") (pinfunction "PA2_16") (pintype "bidirectional"))
    )
    (net (code "73") (name "/VIN_ADC") (class "Default")
      (node (ref "C12") (pin "2") (pinfunction "2_2") (pintype "passive"))
      (node (ref "DE_VIN_ADC") (pin "1") (pinfunction "1_1") (pintype "passive"))
      (node (ref "R18") (pin "1") (pinfunction "1_1") (pintype "passive"))
      (node (ref "R19") (pin "2") (pinfunction "2_2") (pintype "passive"))
    )
    (net (code "74") (name "GND") (class "Default")
      (node (ref "AMS1") (pin "1") (pinfunction "GND_1") (pintype "passive"))
      (node (ref "C1") (pin "1") (pinfunction "1_1") (pintype "passive"))
      (node (ref "C10") (pin "2") (pinfunction "2_2") (pintype "passive"))
      (node (ref "C11") (pin "1") (pinfunction "1_1") (pintype "passive"))
      (node (ref "C12") (pin "1") (pinfunction "1_1") (pintype "passive"))
      (node (ref "C13") (pin "1") (pinfunction "1_1") (pintype "passive"))
      (node (ref "C14") (pin "1") (pinfunction "1_1") (pintype "passive"))
      (node (ref "C15") (pin "1") (pinfunction "1_1") (pintype "passive"))
      (node (ref "C16") (pin "1") (pinfunction "1_1") (pintype "passive"))
      (node (ref "C17") (pin "2") (pinfunction "2_2") (pintype "passive"))
      (node (ref "C18") (pin "1") (pinfunction "1_1") (pintype "passive"))
      (node (ref "C19") (pin "2") (pinfunction "2_2") (pintype "passive"))
      (node (ref "C2") (pin "1") (pinfunction "1_1") (pintype "passive"))
      (node (ref "C20") (pin "1") (pinfunction "1_1") (pintype "passive"))
      (node (ref "C21") (pin "1") (pinfunction "1_1") (pintype "passive"))
      (node (ref "C22") (pin "1") (pinfunction "1_1") (pintype "passive"))
      (node (ref "C23") (pin "1") (pinfunction "1_1") (pintype "passive"))
      (node (ref "C24") (pin "1") (pinfunction "1_1") (pintype "passive"))
      (node (ref "C25") (pin "1") (pinfunction "1_1") (pintype "passive"))
      (node (ref "C26") (pin "1") (pinfunction "1_1") (pintype "passive"))
      (node (ref "C28") (pin "1") (pinfunction "1_1") (pintype "passive"))
      (node (ref "C29") (pin "1") (pinfunction "1_1") (pintype "passive"))
      (node (ref "C3") (pin "1") (pinfunction "1_1") (pintype "passive"))
      (node (ref "C30") (pin "1") (pinfunction "1_1") (pintype "passive"))
      (node (ref "C31") (pin "1") (pinfunction "1_1") (pintype "passive"))
      (node (ref "C32") (pin "1") (pinfunction "1_1") (pintype "passive"))
      (node (ref "C4") (pin "1") (pinfunction "1_1") (pintype "passive"))
      (node (ref "C5") (pin "1") (pinfunction "1_1") (pintype "passive"))
      (node (ref "C6") (pin "1") (pinfunction "1_1") (pintype "passive"))
      (node (ref "C7") (pin "2") (pinfunction "2_2") (pintype "passive"))
      (node (ref "C8") (pin "2") (pinfunction "2_2") (pintype "passive"))
      (node (ref "C9") (pin "2") (pinfunction "2_2") (pintype "passive"))
      (node (ref "EM1") (pin "5") (pinfunction "5_5") (pintype "passive"))
      (node (ref "EM2") (pin "5") (pinfunction "5_5") (pintype "passive"))
      (node (ref "EM3") (pin "5") (pinfunction "5_5") (pintype "passive"))
      (node (ref "EM4") (pin "5") (pinfunction "5_5") (pintype "passive"))
      (node (ref "JP3") (pin "1") (pinfunction "1_1") (pintype "passive"))
      (node (ref "JP3") (pin "2") (pinfunction "2_2") (pintype "passive"))
      (node (ref "JP3") (pin "3") (pinfunction "3_3") (pintype "passive"))
      (node (ref "JP3") (pin "4") (pinfunction "4_4") (pintype "passive"))
      (node (ref "JP3") (pin "5") (pinfunction "5_5") (pintype "passive"))
      (node (ref "JP_PI") (pin "2") (pinfunction "2_2") (pintype "passive"))
      (node (ref "JP_SWD") (pin "4") (pinfunction "4_4") (pintype "passive"))
      (node (ref "K1") (pin "2") (pinfunction "2_2") (pintype "passive"))
      (node (ref "K1") (pin "4") (pinfunction "4_4") (pintype "passive"))
      (node (ref "K2") (pin "2") (pinfunction "2_2") (pintype "passive"))
      (node (ref "K2") (pin "4") (pinfunction "4_4") (pintype "passive"))
      (node (ref "K_RESET") (pin "2") (pinfunction "2_2") (pintype "passive"))
      (node (ref "K_RESET") (pin "4") (pinfunction "4_4") (pintype "passive"))
      (node (ref "LED_PW") (pin "2") (pinfunction "K_2") (pintype "passive"))
      (node (ref "MP1") (pin "1") (pinfunction "AAM_1") (pintype "passive"))
      (node (ref "MP1") (pin "4") (pinfunction "GND_4") (pintype "passive"))
      (node (ref "R11") (pin "1") (pinfunction "1_1") (pintype "passive"))
      (node (ref "R12") (pin "2") (pinfunction "2_2") (pintype "passive"))
      (node (ref "R19") (pin "1") (pinfunction "1_1") (pintype "passive"))
      (node (ref "R2") (pin "1") (pinfunction "1_1") (pintype "passive"))
      (node (ref "R21") (pin "2") (pinfunction "2_2") (pintype "passive"))
      (node (ref "R3") (pin "1") (pinfunction "1_1") (pintype "passive"))
      (node (ref "R9") (pin "2") (pinfunction "2_2") (pintype "passive"))
      (node (ref "TP_GND") (pin "1") (pinfunction "1_1") (pintype "passive"))
      (node (ref "U1") (pin "29") (pinfunction "HEAT_TAB_29") (pintype "passive"))
      (node (ref "U1") (pin "3") (pinfunction "GND_3") (pintype "passive"))
      (node (ref "U2") (pin "12") (pinfunction "VSSA_12") (pintype "power_in"))
      (node (ref "U2") (pin "18") (pinfunction "VSS_4_18") (pintype "power_in"))
      (node (ref "U2") (pin "31") (pinfunction "VSS_1_31") (pintype "power_in"))
      (node (ref "U2") (pin "47") (pinfunction "VSS_2_47") (pintype "power_in"))
      (node (ref "U2") (pin "63") (pinfunction "VSS_3_63") (pintype "power_in"))
      (node (ref "U3") (pin "1") (pinfunction "CLKIN_1") (pintype "passive"))
      (node (ref "U3") (pin "11") (pinfunction "FSYNC_11") (pintype "passive"))
      (node (ref "U3") (pin "18") (pinfunction "GND_18") (pintype "passive"))
      (node (ref "U4") (pin "10") (pinfunction "PGND2_10") (pintype "passive"))
      (node (ref "U4") (pin "18") (pinfunction "GND_18") (pintype "passive"))
      (node (ref "U4") (pin "3") (pinfunction "PGND1_3") (pintype "passive"))
      (node (ref "U4") (pin "4") (pinfunction "PGND1_4") (pintype "passive"))
      (node (ref "U4") (pin "9") (pinfunction "PGND2_9") (pintype "passive"))
      (node (ref "U5") (pin "10") (pinfunction "PGND2_10") (pintype "passive"))
      (node (ref "U5") (pin "18") (pinfunction "GND_18") (pintype "passive"))
      (node (ref "U5") (pin "3") (pinfunction "PGND1_3") (pintype "passive"))
      (node (ref "U5") (pin "4") (pinfunction "PGND1_4") (pintype "passive"))
      (node (ref "U5") (pin "9") (pinfunction "PGND2_9") (pintype "passive"))
      (node (ref "U6") (pin "2") (pinfunction "GND_2") (pintype "passive"))
      (node (ref "USB1") (pin "1") (pinfunction "SH1_1") (pintype "passive"))
      (node (ref "USB1") (pin "2") (pinfunction "SH2_2") (pintype "passive"))
      (node (ref "USB1") (pin "3") (pinfunction "SH3_3") (pintype "passive"))
      (node (ref "USB1") (pin "4") (pinfunction "SH4_4") (pintype "passive"))
      (node (ref "USB1") (pin "A1") (pinfunction "GND_A1") (pintype "passive"))
      (node (ref "USB1") (pin "A12") (pinfunction "GND_A12") (pintype "passive"))
      (node (ref "USB1") (pin "B1") (pinfunction "GND_B1") (pintype "passive"))
      (node (ref "USB1") (pin "B12") (pinfunction "GND_B12") (pintype "passive"))
      (node (ref "VIN1") (pin "1") (pinfunction "1_1") (pintype "passive"))
      (node (ref "X1") (pin "2") (pinfunction "2_2") (pintype "passive"))
      (node (ref "X1") (pin "4") (pinfunction "4_4") (pintype "passive"))
    )
    (net (code "75") (name "Net-(D2-K)") (class "Default")
      (node (ref "D2") (pin "2") (pinfunction "K_2") (pintype "passive"))
      (node (ref "Q1") (pin "3") (pinfunction "C_3") (pintype "passive"))
      (node (ref "R4") (pin "2") (pinfunction "2_2") (pintype "passive"))
    )
    (net (code "76") (name "Net-(LED_BLUE-A)") (class "Default")
      (node (ref "LED_BLUE") (pin "1") (pinfunction "A_1") (pintype "passive"))
      (node (ref "R16") (pin "1") (pinfunction "1_1") (pintype "passive"))
    )
    (net (code "77") (name "Net-(LED_GREEN-A)") (class "Default")
      (node (ref "LED_GREEN") (pin "1") (pinfunction "A_1") (pintype "passive"))
      (node (ref "R15") (pin "1") (pinfunction "1_1") (pintype "passive"))
    )
    (net (code "78") (name "Net-(LED_PW-A)") (class "Default")
      (node (ref "LED_PW") (pin "1") (pinfunction "A_1") (pintype "passive"))
      (node (ref "R17") (pin "1") (pinfunction "1_1") (pintype "passive"))
    )
    (net (code "79") (name "Net-(MP1-BST)") (class "Default")
      (node (ref "C33") (pin "2") (pinfunction "2_2") (pintype "passive"))
      (node (ref "MP1") (pin "5") (pinfunction "BST_5") (pintype "passive"))
    )
    (net (code "80") (name "Net-(MP1-EN{slash}SYNC)") (class "Default")
      (node (ref "MP1") (pin "6") (pinfunction "EN/SYNC_6") (pintype "passive"))
      (node (ref "R22") (pin "1") (pinfunction "1_1") (pintype "passive"))
    )
    (net (code "81") (name "Net-(MP1-FB)") (class "Default")
      (node (ref "C27") (pin "1") (pinfunction "1_1") (pintype "passive"))
      (node (ref "MP1") (pin "8") (pinfunction "FB_8") (pintype "passive"))
      (node (ref "R20") (pin "2") (pinfunction "2_2") (pintype "passive"))
      (node (ref "R21") (pin "1") (pinfunction "1_1") (pintype "passive"))
    )
    (net (code "82") (name "Net-(MP1-SW)") (class "Default")
      (node (ref "C33") (pin "1") (pinfunction "1_1") (pintype "passive"))
      (node (ref "L1") (pin "2") (pinfunction "2_2") (pintype "passive"))
      (node (ref "MP1") (pin "3") (pinfunction "SW_3") (pintype "passive"))
    )
    (net (code "83") (name "Net-(MP1-VCC)") (class "Default")
      (node (ref "C30") (pin "2") (pinfunction "2_2") (pintype "passive"))
      (node (ref "MP1") (pin "7") (pinfunction "VCC_7") (pintype "passive"))
    )
    (net (code "84") (name "Net-(Q1-B)") (class "Default")
      (node (ref "Q1") (pin "1") (pinfunction "B_1") (pintype "passive"))
      (node (ref "R5") (pin "2") (pinfunction "2_2") (pintype "passive"))
    )
    (net (code "85") (name "Net-(Q2-B)") (class "Default")
      (node (ref "Q2") (pin "1") (pinfunction "B_1") (pintype "passive"))
      (node (ref "R6") (pin "2") (pinfunction "2_2") (pintype "passive"))
    )
    (net (code "86") (name "Net-(Q2-C)") (class "Default")
      (node (ref "Q2") (pin "3") (pinfunction "C_3") (pintype "passive"))
      (node (ref "R7") (pin "1") (pinfunction "1_1") (pintype "passive"))
    )
    (net (code "87") (name "Net-(S1-Pad2)") (class "Default")
      (node (ref "S1") (pin "2") (pinfunction "2_2") (pintype "passive"))
      (node (ref "VIN1") (pin "2") (pinfunction "2_2") (pintype "passive"))
    )
    (net (code "88") (name "Net-(U1-*RST)") (class "Default")
      (node (ref "R1") (pin "1") (pinfunction "1_1") (pintype "passive"))
      (node (ref "U1") (pin "9") (pinfunction "*RST_9") (pintype "passive"))
    )
    (net (code "89") (name "Net-(U3-AD0)") (class "Default")
      (node (ref "R11") (pin "2") (pinfunction "2_2") (pintype "passive"))
      (node (ref "U3") (pin "9") (pinfunction "AD0_9") (pintype "passive"))
    )
    (net (code "90") (name "Net-(U3-CPOUT)") (class "Default")
      (node (ref "C7") (pin "1") (pinfunction "1_1") (pintype "passive"))
      (node (ref "U3") (pin "20") (pinfunction "CPOUT_20") (pintype "passive"))
    )
    (net (code "91") (name "Net-(U3-REGOUT)") (class "Default")
      (node (ref "C6") (pin "2") (pinfunction "2_2") (pintype "passive"))
      (node (ref "U3") (pin "10") (pinfunction "REGOUT_10") (pintype "passive"))
    )
    (net (code "92") (name "Net-(USB1-CC1)") (class "Default")
      (node (ref "R2") (pin "2") (pinfunction "2_2") (pintype "passive"))
      (node (ref "USB1") (pin "A5") (pinfunction "CC1_A5") (pintype "passive"))
    )
    (net (code "93") (name "Net-(USB1-CC2)") (class "Default")
      (node (ref "R3") (pin "2") (pinfunction "2_2") (pintype "passive"))
      (node (ref "USB1") (pin "B5") (pinfunction "CC2_B5") (pintype "passive"))
    )
    (net (code "94") (name "USB_5V") (class "Default")
      (node (ref "F1") (pin "1") (pinfunction "1_1") (pintype "passive"))
      (node (ref "R1") (pin "2") (pinfunction "2_2") (pintype "passive"))
      (node (ref "TP_USB_5V") (pin "1") (pinfunction "1_1") (pintype "passive"))
      (node (ref "U1") (pin "7") (pinfunction "REGIN_7") (pintype "passive"))
      (node (ref "U1") (pin "8") (pinfunction "VBUS_8") (pintype "passive"))
      (node (ref "USB1") (pin "A4") (pinfunction "VBUS_A4") (pintype "passive"))
      (node (ref "USB1") (pin "A9") (pinfunction "VBUS_A9") (pintype "passive"))
      (node (ref "USB1") (pin "B4") (pinfunction "VBUS_B4") (pintype "passive"))
      (node (ref "USB1") (pin "B9") (pinfunction "VBUS_B9") (pintype "passive"))
    )
    (net (code "95") (name "VCC3V3") (class "Default")
      (node (ref "AMS1") (pin "2") (pinfunction "Vout_2") (pintype "passive"))
      (node (ref "AMS1") (pin "4") (pinfunction "Vout_4") (pintype "passive"))
      (node (ref "C21") (pin "2") (pinfunction "2_2") (pintype "passive"))
      (node (ref "C22") (pin "2") (pinfunction "2_2") (pintype "passive"))
      (node (ref "C23") (pin "2") (pinfunction "2_2") (pintype "passive"))
      (node (ref "C24") (pin "2") (pinfunction "2_2") (pintype "passive"))
      (node (ref "C25") (pin "2") (pinfunction "2_2") (pintype "passive"))
      (node (ref "C26") (pin "2") (pinfunction "2_2") (pintype "passive"))
      (node (ref "C3") (pin "2") (pinfunction "2_2") (pintype "passive"))
      (node (ref "C4") (pin "2") (pinfunction "2_2") (pintype "passive"))
      (node (ref "C5") (pin "2") (pinfunction "2_2") (pintype "passive"))
      (node (ref "C8") (pin "1") (pinfunction "1_1") (pintype "passive"))
      (node (ref "JP2") (pin "1") (pinfunction "1_1") (pintype "passive"))
      (node (ref "JP2") (pin "2") (pinfunction "2_2") (pintype "passive"))
      (node (ref "JP2") (pin "3") (pinfunction "3_3") (pintype "passive"))
      (node (ref "JP2") (pin "4") (pinfunction "4_4") (pintype "passive"))
      (node (ref "JP2") (pin "5") (pinfunction "5_5") (pintype "passive"))
      (node (ref "JP_SWD") (pin "1") (pinfunction "1_1") (pintype "passive"))
      (node (ref "Q2") (pin "2") (pinfunction "E_2") (pintype "passive"))
      (node (ref "R10") (pin "2") (pinfunction "2_2") (pintype "passive"))
      (node (ref "R14") (pin "2") (pinfunction "2_2") (pintype "passive"))
      (node (ref "R15") (pin "2") (pinfunction "2_2") (pintype "passive"))
      (node (ref "R16") (pin "2") (pinfunction "2_2") (pintype "passive"))
      (node (ref "R17") (pin "2") (pinfunction "2_2") (pintype "passive"))
      (node (ref "R4") (pin "1") (pinfunction "1_1") (pintype "passive"))
      (node (ref "R8") (pin "2") (pinfunction "2_2") (pintype "passive"))
      (node (ref "TP_VCC3V3") (pin "1") (pinfunction "1_1") (pintype "passive"))
      (node (ref "U2") (pin "1") (pinfunction "VBAT_1") (pintype "power_in"))
      (node (ref "U2") (pin "13") (pinfunction "VDDA_13") (pintype "power_in"))
      (node (ref "U2") (pin "19") (pinfunction "VDD_4_19") (pintype "power_in"))
      (node (ref "U2") (pin "32") (pinfunction "VDD_1_32") (pintype "power_in"))
      (node (ref "U2") (pin "48") (pinfunction "VDD_2_48") (pintype "power_in"))
      (node (ref "U2") (pin "64") (pinfunction "VDD_3_64") (pintype "power_in"))
      (node (ref "U3") (pin "13") (pinfunction "VDD_13") (pintype "passive"))
      (node (ref "U3") (pin "8") (pinfunction "VLogic_8") (pintype "passive"))
      (node (ref "U6") (pin "3") (pinfunction "VCC_3") (pintype "passive"))
    )
    (net (code "96") (name "VCC5V") (class "Default")
      (node (ref "AMS1") (pin "3") (pinfunction "Vin_3") (pintype "passive"))
      (node (ref "C1") (pin "2") (pinfunction "2_2") (pintype "passive"))
      (node (ref "C17") (pin "1") (pinfunction "1_1") (pintype "passive"))
      (node (ref "C18") (pin "2") (pinfunction "2_2") (pintype "passive"))
      (node (ref "C19") (pin "1") (pinfunction "1_1") (pintype "passive"))
      (node (ref "C2") (pin "2") (pinfunction "2_2") (pintype "passive"))
      (node (ref "C20") (pin "2") (pinfunction "2_2") (pintype "passive"))
      (node (ref "C27") (pin "2") (pinfunction "2_2") (pintype "passive"))
      (node (ref "C31") (pin "2") (pinfunction "2_2") (pintype "passive"))
      (node (ref "C32") (pin "2") (pinfunction "2_2") (pintype "passive"))
      (node (ref "EM1") (pin "2") (pinfunction "2_2") (pintype "passive"))
      (node (ref "EM2") (pin "2") (pinfunction "2_2") (pintype "passive"))
      (node (ref "EM3") (pin "2") (pinfunction "2_2") (pintype "passive"))
      (node (ref "EM4") (pin "2") (pinfunction "2_2") (pintype "passive"))
      (node (ref "F1") (pin "2") (pinfunction "2_2") (pintype "passive"))
      (node (ref "JP1") (pin "1") (pinfunction "1_1") (pintype "passive"))
      (node (ref "JP1") (pin "2") (pinfunction "2_2") (pintype "passive"))
      (node (ref "JP1") (pin "3") (pinfunction "3_3") (pintype "passive"))
      (node (ref "JP1") (pin "4") (pinfunction "4_4") (pintype "passive"))
      (node (ref "JP1") (pin "5") (pinfunction "5_5") (pintype "passive"))
      (node (ref "JP_PI") (pin "1") (pinfunction "1_1") (pintype "passive"))
      (node (ref "L1") (pin "1") (pinfunction "1_1") (pintype "passive"))
      (node (ref "R20") (pin "1") (pinfunction "1_1") (pintype "passive"))
      (node (ref "RP12") (pin "5") (pinfunction "5_5") (pintype "passive"))
      (node (ref "RP12") (pin "6") (pinfunction "6_6") (pintype "passive"))
      (node (ref "RP12") (pin "7") (pinfunction "7_7") (pintype "passive"))
      (node (ref "RP12") (pin "8") (pinfunction "8_8") (pintype "passive"))
      (node (ref "RP34") (pin "5") (pinfunction "5_5") (pintype "passive"))
      (node (ref "RP34") (pin "6") (pinfunction "6_6") (pintype "passive"))
      (node (ref "RP34") (pin "7") (pinfunction "7_7") (pintype "passive"))
      (node (ref "RP34") (pin "8") (pinfunction "8_8") (pintype "passive"))
      (node (ref "TP_VCC5V") (pin "1") (pinfunction "1_1") (pintype "passive"))
      (node (ref "U4") (pin "19") (pinfunction "STBY_19") (pintype "passive"))
      (node (ref "U4") (pin "20") (pinfunction "VCC_20") (pintype "passive"))
      (node (ref "U5") (pin "19") (pinfunction "STBY_19") (pintype "passive"))
      (node (ref "U5") (pin "20") (pinfunction "VCC_20") (pintype "passive"))
    )
    (net (code "97") (name "VCC12V") (class "Default")
      (node (ref "C13") (pin "2") (pinfunction "2_2") (pintype "passive"))
      (node (ref "C14") (pin "2") (pinfunction "2_2") (pintype "passive"))
      (node (ref "C15") (pin "2") (pinfunction "2_2") (pintype "passive"))
      (node (ref "C16") (pin "2") (pinfunction "2_2") (pintype "passive"))
      (node (ref "C28") (pin "2") (pinfunction "2_2") (pintype "passive"))
      (node (ref "C29") (pin "2") (pinfunction "2_2") (pintype "passive"))
      (node (ref "MP1") (pin "2") (pinfunction "IN_2") (pintype "passive"))
      (node (ref "R18") (pin "2") (pinfunction "2_2") (pintype "passive"))
      (node (ref "R22") (pin "2") (pinfunction "2_2") (pintype "passive"))
      (node (ref "S1") (pin "3") (pinfunction "3_3") (pintype "passive"))
      (node (ref "TP_VCC12V") (pin "1") (pinfunction "1_1") (pintype "passive"))
      (node (ref "U4") (pin "13") (pinfunction "VM2_13") (pintype "passive"))
      (node (ref "U4") (pin "14") (pinfunction "VM3_14") (pintype "passive"))
      (node (ref "U4") (pin "24") (pinfunction "VM1_24") (pintype "passive"))
      (node (ref "U5") (pin "13") (pinfunction "VM2_13") (pintype "passive"))
      (node (ref "U5") (pin "14") (pinfunction "VM3_14") (pintype "passive"))
      (node (ref "U5") (pin "24") (pinfunction "VM1_24") (pintype "passive"))
    )
    (net (code "98") (name "unconnected-(S1-Pad1)") (class "Default")
      (node (ref "S1") (pin "1") (pinfunction "1_1") (pintype "passive"))
    )
    (net (code "99") (name "unconnected-(U1-*SUSPEND-Pad11)") (class "Default")
      (node (ref "U1") (pin "11") (pinfunction "*SUSPEND_11") (pintype "passive"))
    )
    (net (code "100") (name "unconnected-(U1-CTS-Pad23)") (class "Default")
      (node (ref "U1") (pin "23") (pinfunction "CTS_23") (pintype "passive"))
    )
    (net (code "101") (name "unconnected-(U1-DCD-Pad1)") (class "Default")
      (node (ref "U1") (pin "1") (pinfunction "DCD_1") (pintype "passive"))
    )
    (net (code "102") (name "unconnected-(U1-DSR-Pad27)") (class "Default")
      (node (ref "U1") (pin "27") (pinfunction "DSR_27") (pintype "passive"))
    )
    (net (code "103") (name "unconnected-(U1-NC-Pad10)") (class "Default")
      (node (ref "U1") (pin "10") (pinfunction "NC_10") (pintype "passive"))
    )
    (net (code "104") (name "unconnected-(U1-NC-Pad13)") (class "Default")
      (node (ref "U1") (pin "13") (pinfunction "NC_13") (pintype "passive"))
    )
    (net (code "105") (name "unconnected-(U1-NC-Pad14)") (class "Default")
      (node (ref "U1") (pin "14") (pinfunction "NC_14") (pintype "passive"))
    )
    (net (code "106") (name "unconnected-(U1-NC-Pad15)") (class "Default")
      (node (ref "U1") (pin "15") (pinfunction "NC_15") (pintype "passive"))
    )
    (net (code "107") (name "unconnected-(U1-NC-Pad16)") (class "Default")
      (node (ref "U1") (pin "16") (pinfunction "NC_16") (pintype "passive"))
    )
    (net (code "108") (name "unconnected-(U1-NC-Pad17)") (class "Default")
      (node (ref "U1") (pin "17") (pinfunction "NC_17") (pintype "passive"))
    )
    (net (code "109") (name "unconnected-(U1-NC-Pad18)") (class "Default")
      (node (ref "U1") (pin "18") (pinfunction "NC_18") (pintype "passive"))
    )
    (net (code "110") (name "unconnected-(U1-NC-Pad19)") (class "Default")
      (node (ref "U1") (pin "19") (pinfunction "NC_19") (pintype "passive"))
    )
    (net (code "111") (name "unconnected-(U1-NC-Pad20)") (class "Default")
      (node (ref "U1") (pin "20") (pinfunction "NC_20") (pintype "passive"))
    )
    (net (code "112") (name "unconnected-(U1-NC-Pad21)") (class "Default")
      (node (ref "U1") (pin "21") (pinfunction "NC_21") (pintype "passive"))
    )
    (net (code "113") (name "unconnected-(U1-NC-Pad22)") (class "Default")
      (node (ref "U1") (pin "22") (pinfunction "NC_22") (pintype "passive"))
    )
    (net (code "114") (name "unconnected-(U1-RI-Pad2)") (class "Default")
      (node (ref "U1") (pin "2") (pinfunction "RI_2") (pintype "passive"))
    )
    (net (code "115") (name "unconnected-(U1-SUSPEND-Pad12)") (class "Default")
      (node (ref "U1") (pin "12") (pinfunction "SUSPEND_12") (pintype "passive"))
    )
    (net (code "116") (name "unconnected-(U1-VDD-Pad6)") (class "Default")
      (node (ref "U1") (pin "6") (pinfunction "VDD_6") (pintype "passive"))
    )
    (net (code "117") (name "unconnected-(U3-A_CL-Pad7)") (class "Default")
      (node (ref "U3") (pin "7") (pinfunction "A_CL_7") (pintype "passive+no_connect"))
    )
    (net (code "118") (name "unconnected-(U3-A_DA-Pad6)") (class "Default")
      (node (ref "U3") (pin "6") (pinfunction "A_DA_6") (pintype "passive+no_connect"))
    )
    (net (code "119") (name "unconnected-(U3-CLKOUT-Pad22)") (class "Default")
      (node (ref "U3") (pin "22") (pinfunction "CLKOUT_22") (pintype "passive+no_connect"))
    )
    (net (code "120") (name "unconnected-(U3-NC-Pad2)") (class "Default")
      (node (ref "U3") (pin "2") (pinfunction "NC_2") (pintype "passive+no_connect"))
    )
    (net (code "121") (name "unconnected-(U3-NC-Pad3)") (class "Default")
      (node (ref "U3") (pin "3") (pinfunction "NC_3") (pintype "passive+no_connect"))
    )
    (net (code "122") (name "unconnected-(U3-NC-Pad4)") (class "Default")
      (node (ref "U3") (pin "4") (pinfunction "NC_4") (pintype "passive+no_connect"))
    )
    (net (code "123") (name "unconnected-(U3-NC-Pad5)") (class "Default")
      (node (ref "U3") (pin "5") (pinfunction "NC_5") (pintype "passive+no_connect"))
    )
    (net (code "124") (name "unconnected-(U3-NC-Pad14)") (class "Default")
      (node (ref "U3") (pin "14") (pinfunction "NC_14") (pintype "passive"))
    )
    (net (code "125") (name "unconnected-(U3-NC-Pad15)") (class "Default")
      (node (ref "U3") (pin "15") (pinfunction "NC_15") (pintype "passive"))
    )
    (net (code "126") (name "unconnected-(U3-NC-Pad16)") (class "Default")
      (node (ref "U3") (pin "16") (pinfunction "NC_16") (pintype "passive"))
    )
    (net (code "127") (name "unconnected-(U3-NC-Pad17)") (class "Default")
      (node (ref "U3") (pin "17") (pinfunction "NC_17") (pintype "passive"))
    )
    (net (code "128") (name "unconnected-(U3-RESV-Pad19)") (class "Default")
      (node (ref "U3") (pin "19") (pinfunction "RESV_19") (pintype "passive+no_connect"))
    )
    (net (code "129") (name "unconnected-(U3-RESV-Pad21)") (class "Default")
      (node (ref "U3") (pin "21") (pinfunction "RESV_21") (pintype "passive+no_connect"))
    )
    (net (code "130") (name "unconnected-(U6-NC-Pad5)") (class "Default")
      (node (ref "U6") (pin "5") (pinfunction "NC_5") (pintype "passive"))
    )
    (net (code "131") (name "unconnected-(U6-NC-Pad8)") (class "Default")
      (node (ref "U6") (pin "8") (pinfunction "NC_8") (pintype "passive"))
    )
    (net (code "132") (name "unconnected-(USB1-RX1+-PadB11)") (class "Default")
      (node (ref "USB1") (pin "B11") (pinfunction "RX1+_B11") (pintype "passive"))
    )
    (net (code "133") (name "unconnected-(USB1-RX1--PadB10)") (class "Default")
      (node (ref "USB1") (pin "B10") (pinfunction "RX1-_B10") (pintype "passive"))
    )
    (net (code "134") (name "unconnected-(USB1-RX2+-PadA11)") (class "Default")
      (node (ref "USB1") (pin "A11") (pinfunction "RX2+_A11") (pintype "passive"))
    )
    (net (code "135") (name "unconnected-(USB1-RX2--PadA10)") (class "Default")
      (node (ref "USB1") (pin "A10") (pinfunction "RX2-_A10") (pintype "passive"))
    )
    (net (code "136") (name "unconnected-(USB1-SBU1-PadA8)") (class "Default")
      (node (ref "USB1") (pin "A8") (pinfunction "SBU1_A8") (pintype "passive"))
    )
    (net (code "137") (name "unconnected-(USB1-SBU2-PadB8)") (class "Default")
      (node (ref "USB1") (pin "B8") (pinfunction "SBU2_B8") (pintype "passive"))
    )
    (net (code "138") (name "unconnected-(USB1-TX1+-PadA2)") (class "Default")
      (node (ref "USB1") (pin "A2") (pinfunction "TX1+_A2") (pintype "passive"))
    )
    (net (code "139") (name "unconnected-(USB1-TX1--PadA3)") (class "Default")
      (node (ref "USB1") (pin "A3") (pinfunction "TX1-_A3") (pintype "passive"))
    )
    (net (code "140") (name "unconnected-(USB1-TX2+-PadB2)") (class "Default")
      (node (ref "USB1") (pin "B2") (pinfunction "TX2+_B2") (pintype "passive"))
    )
    (net (code "141") (name "unconnected-(USB1-TX2--PadB3)") (class "Default")
      (node (ref "USB1") (pin "B3") (pinfunction "TX2-_B3") (pintype "passive"))
    )
  )
)
